# DiveComputer_STM32.net
KiCad netlist of a schematic drawn in EAGLE
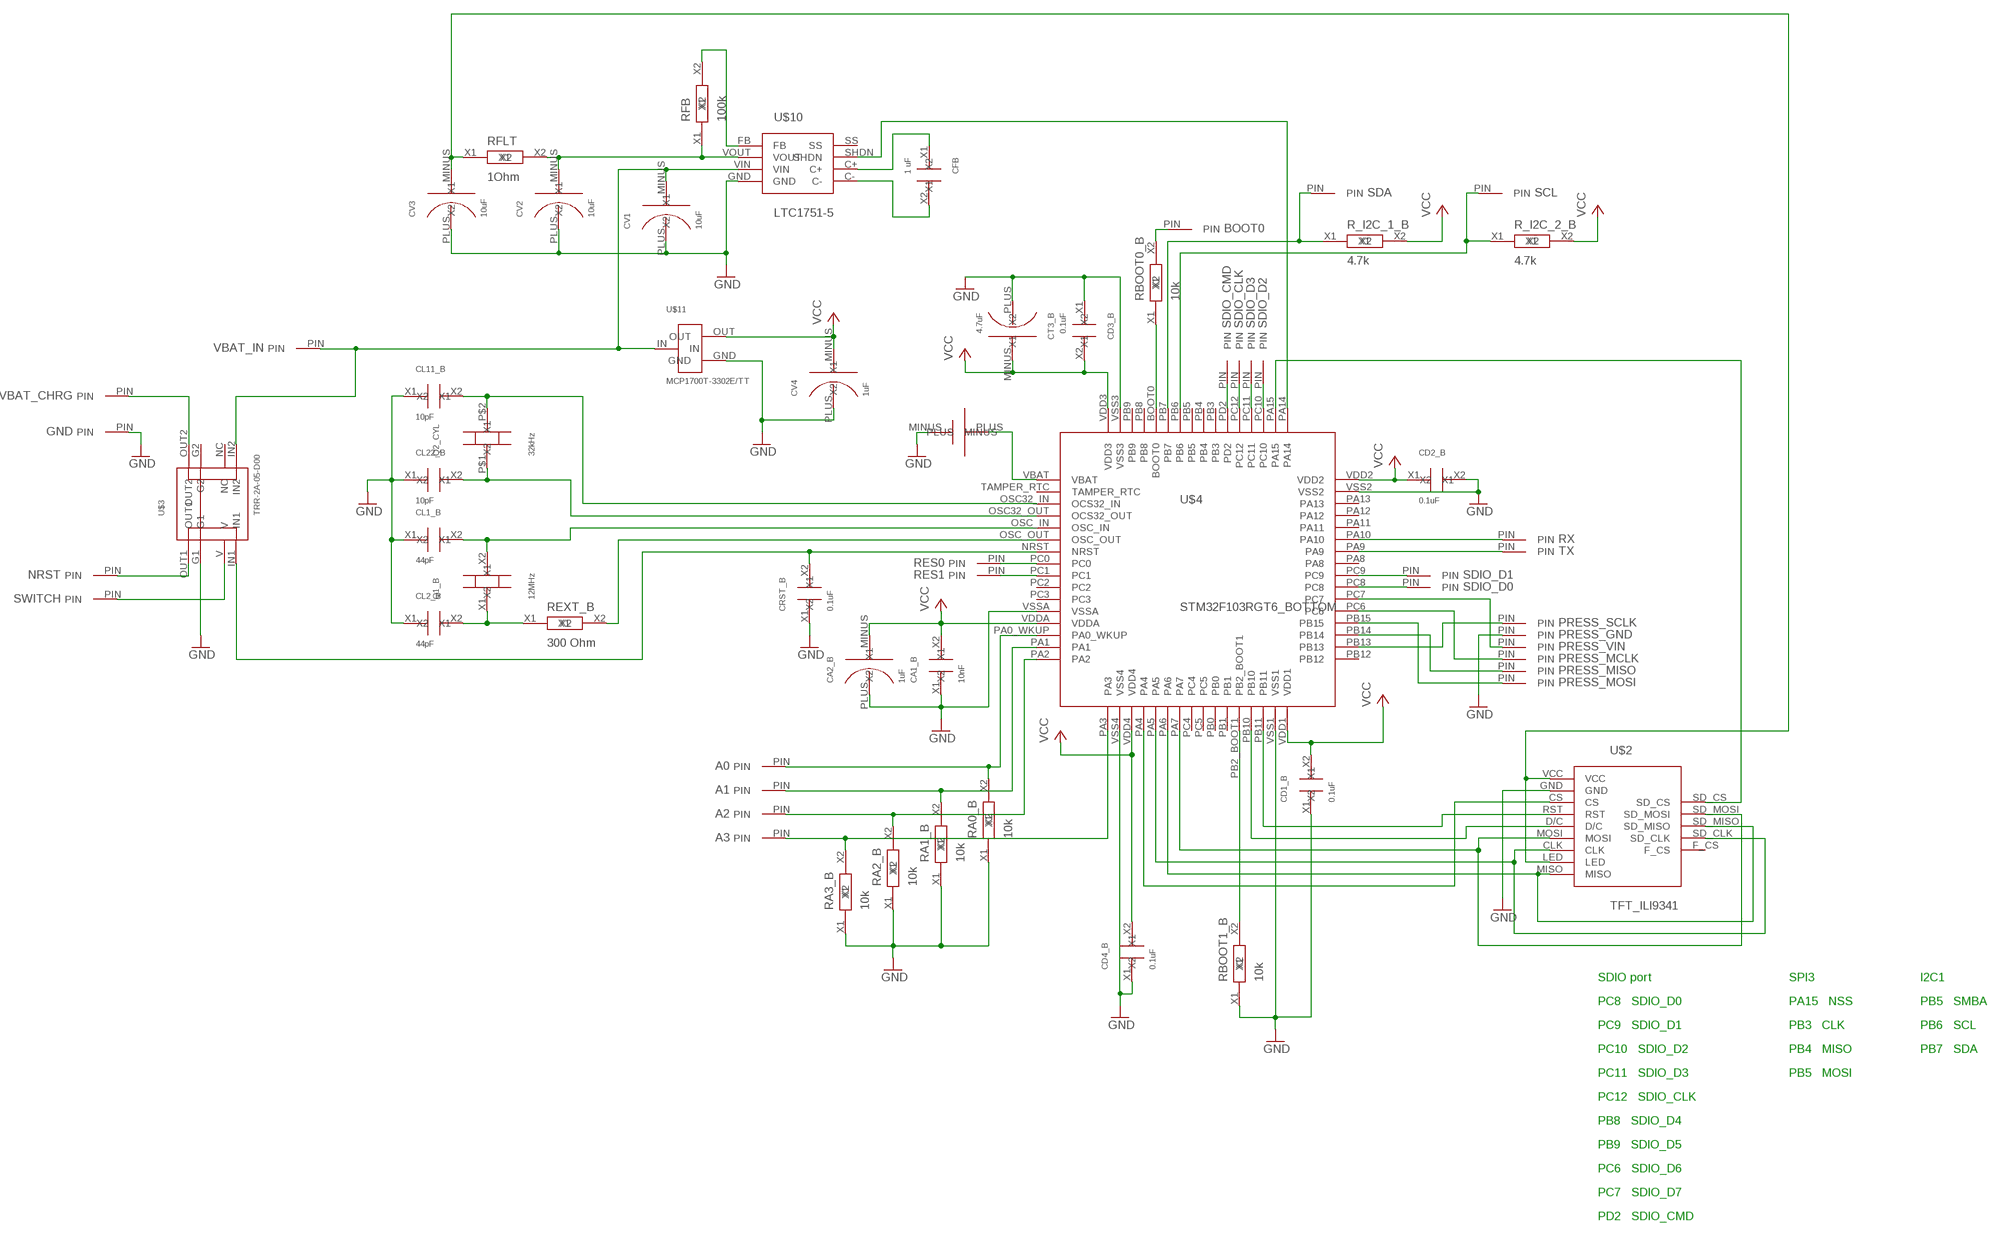
[diagram p0: schematic, sheet 1]

(export (version "E")
  (design (tool "Eeschema 10.0.6"))
  (components
    (comp (ref "A0")
      (value "PIN")
      (footprint "eagle-import:PIN")
      (libsource (lib "eagle-import") (part "PIN"))
    )
    (comp (ref "A1")
      (value "PIN")
      (footprint "eagle-import:PIN")
      (libsource (lib "eagle-import") (part "PIN"))
    )
    (comp (ref "A2")
      (value "PIN")
      (footprint "eagle-import:PIN")
      (libsource (lib "eagle-import") (part "PIN"))
    )
    (comp (ref "A3")
      (value "PIN")
      (footprint "eagle-import:PIN")
      (libsource (lib "eagle-import") (part "PIN"))
    )
    (comp (ref "BOOT0")
      (value "PIN")
      (footprint "eagle-import:PIN")
      (libsource (lib "eagle-import") (part "PIN"))
    )
    (comp (ref "CA1_B")
      (value "10nF")
      (footprint "eagle-import:SMD_2.1X1.25_BOTTOM")
      (libsource (lib "eagle-import") (part "C_SMD_2.1X1.25_BOTTOM"))
    )
    (comp (ref "CA2_B")
      (value "1uF")
      (footprint "eagle-import:C_SMD_TA_A_BOTTOM")
      (libsource (lib "eagle-import") (part "C_SMD_TA_A_BOTTOM"))
    )
    (comp (ref "CD1_B")
      (value "0.1uF")
      (footprint "eagle-import:SMD_2.1X1.25_BOTTOM")
      (libsource (lib "eagle-import") (part "C_SMD_2.1X1.25_BOTTOM"))
    )
    (comp (ref "CD2_B")
      (value "0.1uF")
      (footprint "eagle-import:SMD_2.1X1.25_BOTTOM")
      (libsource (lib "eagle-import") (part "C_SMD_2.1X1.25_BOTTOM"))
    )
    (comp (ref "CD3_B")
      (value "0.1uF")
      (footprint "eagle-import:SMD_2.1X1.25_BOTTOM")
      (libsource (lib "eagle-import") (part "C_SMD_2.1X1.25_BOTTOM"))
    )
    (comp (ref "CD4_B")
      (value "0.1uF")
      (footprint "eagle-import:SMD_2.1X1.25_BOTTOM")
      (libsource (lib "eagle-import") (part "C_SMD_2.1X1.25_BOTTOM"))
    )
    (comp (ref "CFB")
      (value "1 uF")
      (footprint "eagle-import:SMD_2.1X1.25")
      (libsource (lib "eagle-import") (part "C_SMD_2.1X1.25"))
    )
    (comp (ref "CL1_B")
      (value "44pF")
      (footprint "eagle-import:SMD_2.1X1.25_BOTTOM")
      (libsource (lib "eagle-import") (part "C_SMD_2.1X1.25_BOTTOM"))
    )
    (comp (ref "CL2_B")
      (value "44pF")
      (footprint "eagle-import:SMD_2.1X1.25_BOTTOM")
      (libsource (lib "eagle-import") (part "C_SMD_2.1X1.25_BOTTOM"))
    )
    (comp (ref "CL11_B")
      (value "10pF")
      (footprint "eagle-import:SMD_2.1X1.25_BOTTOM")
      (libsource (lib "eagle-import") (part "C_SMD_2.1X1.25_BOTTOM"))
    )
    (comp (ref "CL22_B")
      (value "10pF")
      (footprint "eagle-import:SMD_2.1X1.25_BOTTOM")
      (libsource (lib "eagle-import") (part "C_SMD_2.1X1.25_BOTTOM"))
    )
    (comp (ref "CRST_B")
      (value "0.1uF")
      (footprint "eagle-import:SMD_2.1X1.25_BOTTOM")
      (libsource (lib "eagle-import") (part "C_SMD_2.1X1.25_BOTTOM"))
    )
    (comp (ref "CT3_B")
      (value "4.7uF")
      (footprint "eagle-import:C_SMD_TA_A_BOTTOM")
      (libsource (lib "eagle-import") (part "C_SMD_TA_A_BOTTOM"))
    )
    (comp (ref "CV1")
      (value "10uF")
      (footprint "eagle-import:C_SMD_TA_A")
      (libsource (lib "eagle-import") (part "C_SMD_TA_A"))
    )
    (comp (ref "CV2")
      (value "10uF")
      (footprint "eagle-import:C_SMD_TA_A")
      (libsource (lib "eagle-import") (part "C_SMD_TA_A"))
    )
    (comp (ref "CV3")
      (value "10uF")
      (footprint "eagle-import:C_SMD_TA_A")
      (libsource (lib "eagle-import") (part "C_SMD_TA_A"))
    )
    (comp (ref "CV4")
      (value "1uF")
      (footprint "eagle-import:C_SMD_TA_A")
      (libsource (lib "eagle-import") (part "C_SMD_TA_A"))
    )
    (comp (ref "GND")
      (value "PIN")
      (footprint "eagle-import:PIN")
      (libsource (lib "eagle-import") (part "PIN"))
    )
    (comp (ref "NRST")
      (value "PIN")
      (footprint "eagle-import:PIN")
      (libsource (lib "eagle-import") (part "PIN"))
    )
    (comp (ref "PRESS_GND")
      (value "PIN")
      (footprint "eagle-import:PIN")
      (libsource (lib "eagle-import") (part "PIN"))
    )
    (comp (ref "PRESS_MCLK")
      (value "PIN")
      (footprint "eagle-import:PIN")
      (libsource (lib "eagle-import") (part "PIN"))
    )
    (comp (ref "PRESS_MISO")
      (value "PIN")
      (footprint "eagle-import:PIN")
      (libsource (lib "eagle-import") (part "PIN"))
    )
    (comp (ref "PRESS_MOSI")
      (value "PIN")
      (footprint "eagle-import:PIN")
      (libsource (lib "eagle-import") (part "PIN"))
    )
    (comp (ref "PRESS_SCLK")
      (value "PIN")
      (footprint "eagle-import:PIN")
      (libsource (lib "eagle-import") (part "PIN"))
    )
    (comp (ref "PRESS_VIN")
      (value "PIN")
      (footprint "eagle-import:PIN")
      (libsource (lib "eagle-import") (part "PIN"))
    )
    (comp (ref "Q1_B")
      (value "12MHz")
      (footprint "eagle-import:QUARTZ_SMD_BOTTOM")
      (libsource (lib "eagle-import") (part "QUARTZ_SMD_BOTTOM"))
    )
    (comp (ref "Q2_CYL")
      (value "32kHz")
      (footprint "eagle-import:QUARTZ_CYL")
      (libsource (lib "eagle-import") (part "QUARTZ_CYL"))
    )
    (comp (ref "RA0_B")
      (value "10k")
      (footprint "eagle-import:SMD_2.1X1.25_BOTTOM")
      (libsource (lib "eagle-import") (part "R_SMD_2.1X1.25_BOTTOM"))
    )
    (comp (ref "RA1_B")
      (value "10k")
      (footprint "eagle-import:SMD_2.1X1.25_BOTTOM")
      (libsource (lib "eagle-import") (part "R_SMD_2.1X1.25_BOTTOM"))
    )
    (comp (ref "RA2_B")
      (value "10k")
      (footprint "eagle-import:SMD_2.1X1.25_BOTTOM")
      (libsource (lib "eagle-import") (part "R_SMD_2.1X1.25_BOTTOM"))
    )
    (comp (ref "RA3_B")
      (value "10k")
      (footprint "eagle-import:SMD_2.1X1.25_BOTTOM")
      (libsource (lib "eagle-import") (part "R_SMD_2.1X1.25_BOTTOM"))
    )
    (comp (ref "RBOOT0_B")
      (value "10k")
      (footprint "eagle-import:SMD_2.1X1.25_BOTTOM")
      (libsource (lib "eagle-import") (part "R_SMD_2.1X1.25_BOTTOM"))
    )
    (comp (ref "RBOOT1_B")
      (value "10k")
      (footprint "eagle-import:SMD_2.1X1.25_BOTTOM")
      (libsource (lib "eagle-import") (part "R_SMD_2.1X1.25_BOTTOM"))
    )
    (comp (ref "RES0")
      (value "PIN")
      (footprint "eagle-import:PIN")
      (libsource (lib "eagle-import") (part "PIN"))
    )
    (comp (ref "RES1")
      (value "PIN")
      (footprint "eagle-import:PIN")
      (libsource (lib "eagle-import") (part "PIN"))
    )
    (comp (ref "REXT_B")
      (value "300 Ohm")
      (footprint "eagle-import:SMD_2.1X1.25_BOTTOM")
      (libsource (lib "eagle-import") (part "R_SMD_2.1X1.25_BOTTOM"))
    )
    (comp (ref "RFB")
      (value "100k")
      (footprint "eagle-import:SMD_2.1X1.25")
      (libsource (lib "eagle-import") (part "R_SMD_2.1X1.25"))
    )
    (comp (ref "RFLT")
      (value "1Ohm")
      (footprint "eagle-import:SMD_2.1X1.25")
      (libsource (lib "eagle-import") (part "R_SMD_2.1X1.25"))
    )
    (comp (ref "RX")
      (value "PIN")
      (footprint "eagle-import:PIN")
      (libsource (lib "eagle-import") (part "PIN"))
    )
    (comp (ref "R_I2C_1_B")
      (value "4.7k")
      (footprint "eagle-import:SMD_2.1X1.25_BOTTOM")
      (libsource (lib "eagle-import") (part "R_SMD_2.1X1.25_BOTTOM"))
    )
    (comp (ref "R_I2C_2_B")
      (value "4.7k")
      (footprint "eagle-import:SMD_2.1X1.25_BOTTOM")
      (libsource (lib "eagle-import") (part "R_SMD_2.1X1.25_BOTTOM"))
    )
    (comp (ref "SCL")
      (value "PIN")
      (footprint "eagle-import:PIN")
      (libsource (lib "eagle-import") (part "PIN"))
    )
    (comp (ref "SDA")
      (value "PIN")
      (footprint "eagle-import:PIN")
      (libsource (lib "eagle-import") (part "PIN"))
    )
    (comp (ref "SDIO_CLK")
      (value "PIN")
      (footprint "eagle-import:PIN")
      (libsource (lib "eagle-import") (part "PIN"))
    )
    (comp (ref "SDIO_CMD")
      (value "PIN")
      (footprint "eagle-import:PIN")
      (libsource (lib "eagle-import") (part "PIN"))
    )
    (comp (ref "SDIO_D0")
      (value "PIN")
      (footprint "eagle-import:PIN")
      (libsource (lib "eagle-import") (part "PIN"))
    )
    (comp (ref "SDIO_D1")
      (value "PIN")
      (footprint "eagle-import:PIN")
      (libsource (lib "eagle-import") (part "PIN"))
    )
    (comp (ref "SDIO_D2")
      (value "PIN")
      (footprint "eagle-import:PIN")
      (libsource (lib "eagle-import") (part "PIN"))
    )
    (comp (ref "SDIO_D3")
      (value "PIN")
      (footprint "eagle-import:PIN")
      (libsource (lib "eagle-import") (part "PIN"))
    )
    (comp (ref "SWITCH")
      (value "PIN")
      (footprint "eagle-import:PIN")
      (libsource (lib "eagle-import") (part "PIN"))
    )
    (comp (ref "TX")
      (value "PIN")
      (footprint "eagle-import:PIN")
      (libsource (lib "eagle-import") (part "PIN"))
    )
    (comp (ref "U$1")
      (value "VBAT")
      (footprint "eagle-import:VBAT")
      (libsource (lib "eagle-import") (part "VBAT"))
    )
    (comp (ref "U$2")
      (value "TFT_ILI9341")
      (footprint "eagle-import:TFT_ILI9341")
      (libsource (lib "eagle-import") (part "TFT_ILI9341"))
    )
    (comp (ref "U$3")
      (value "TRR-2A-05-D00")
      (footprint "eagle-import:TRR-2A-05-D00")
      (libsource (lib "eagle-import") (part "TRR-2A-05-D00"))
    )
    (comp (ref "U$4")
      (value "STM32F103RGT6_BOTTOM")
      (footprint "eagle-import:STM32F103RGT6_BOTTOM")
      (libsource (lib "eagle-import") (part "STM32F103RGT6_BOTTOM"))
    )
    (comp (ref "U$10")
      (value "LTC1751-5")
      (footprint "eagle-import:LTC1751-5")
      (libsource (lib "eagle-import") (part "LTC1751-5"))
    )
    (comp (ref "U$11")
      (value "MCP1700T-3302E/TT")
      (footprint "eagle-import:MCP1700T-3302E_TT")
      (libsource (lib "eagle-import") (part "MCP1700T-3302E/TT"))
    )
    (comp (ref "VBAT_CHRG")
      (value "PIN")
      (footprint "eagle-import:PIN")
      (libsource (lib "eagle-import") (part "PIN"))
    )
    (comp (ref "VBAT_IN")
      (value "PIN")
      (footprint "eagle-import:PIN")
      (libsource (lib "eagle-import") (part "PIN"))
    )
  )
  (nets
    (net (code "1") (name "GND") (class "Default")
      (node (ref "CA1_B") (pin "X1") (pinfunction "X1_X1") (pintype "bidirectional"))
      (node (ref "CA2_B") (pin "PLUS") (pinfunction "X1_PLUS") (pintype "bidirectional"))
      (node (ref "CD1_B") (pin "X1") (pinfunction "X1_X1") (pintype "bidirectional"))
      (node (ref "CD2_B") (pin "X2") (pinfunction "X2_X2") (pintype "bidirectional"))
      (node (ref "CD3_B") (pin "X1") (pinfunction "X1_X1") (pintype "bidirectional"))
      (node (ref "CD4_B") (pin "X1") (pinfunction "X1_X1") (pintype "bidirectional"))
      (node (ref "CL11_B") (pin "X1") (pinfunction "X1_X1") (pintype "bidirectional"))
      (node (ref "CL1_B") (pin "X1") (pinfunction "X1_X1") (pintype "bidirectional"))
      (node (ref "CL22_B") (pin "X1") (pinfunction "X1_X1") (pintype "bidirectional"))
      (node (ref "CL2_B") (pin "X1") (pinfunction "X1_X1") (pintype "bidirectional"))
      (node (ref "CRST_B") (pin "X1") (pinfunction "X1_X1") (pintype "bidirectional"))
      (node (ref "CT3_B") (pin "PLUS") (pinfunction "X1_PLUS") (pintype "bidirectional"))
      (node (ref "CV1") (pin "PLUS") (pinfunction "X1_PLUS") (pintype "bidirectional"))
      (node (ref "CV2") (pin "PLUS") (pinfunction "X1_PLUS") (pintype "bidirectional"))
      (node (ref "CV3") (pin "PLUS") (pinfunction "X1_PLUS") (pintype "bidirectional"))
      (node (ref "CV4") (pin "PLUS") (pinfunction "X1_PLUS") (pintype "bidirectional"))
      (node (ref "GND") (pin "PIN") (pinfunction "PIN_PIN") (pintype "bidirectional"))
      (node (ref "PRESS_GND") (pin "PIN") (pinfunction "PIN_PIN") (pintype "bidirectional"))
      (node (ref "RA0_B") (pin "X1") (pinfunction "X1_X1") (pintype "bidirectional"))
      (node (ref "RA1_B") (pin "X1") (pinfunction "X1_X1") (pintype "bidirectional"))
      (node (ref "RA2_B") (pin "X1") (pinfunction "X1_X1") (pintype "bidirectional"))
      (node (ref "RA3_B") (pin "X1") (pinfunction "X1_X1") (pintype "bidirectional"))
      (node (ref "RBOOT1_B") (pin "X1") (pinfunction "X1_X1") (pintype "bidirectional"))
      (node (ref "U$1") (pin "MINUS") (pinfunction "MINUS_MINUS") (pintype "bidirectional"))
      (node (ref "U$10") (pin "GND") (pinfunction "GND_GND") (pintype "bidirectional"))
      (node (ref "U$11") (pin "GND") (pinfunction "GND_GND") (pintype "bidirectional"))
      (node (ref "U$2") (pin "GND") (pinfunction "GND_GND") (pintype "bidirectional"))
      (node (ref "U$3") (pin "G1") (pinfunction "G1_G1") (pintype "bidirectional"))
      (node (ref "U$4") (pin "VSS1") (pinfunction "VSS1_VSS1") (pintype "bidirectional"))
      (node (ref "U$4") (pin "VSS2") (pinfunction "VSS2_VSS2") (pintype "bidirectional"))
      (node (ref "U$4") (pin "VSS3") (pinfunction "VSS3_VSS3") (pintype "bidirectional"))
      (node (ref "U$4") (pin "VSS4") (pinfunction "VSS4_VSS4") (pintype "bidirectional"))
      (node (ref "U$4") (pin "VSSA") (pinfunction "VSSA_VSSA") (pintype "bidirectional"))
    )
    (net (code "2") (name "Net-(A0-PadPIN)") (class "Default")
      (node (ref "A0") (pin "PIN") (pinfunction "PIN_PIN") (pintype "bidirectional"))
      (node (ref "RA0_B") (pin "X2") (pinfunction "X2_X2") (pintype "bidirectional"))
      (node (ref "U$4") (pin "PA0_WKUP") (pinfunction "PA0_WKUP_PA0_WKUP") (pintype "bidirectional"))
    )
    (net (code "3") (name "Net-(A1-PadPIN)") (class "Default")
      (node (ref "A1") (pin "PIN") (pinfunction "PIN_PIN") (pintype "bidirectional"))
      (node (ref "RA1_B") (pin "X2") (pinfunction "X2_X2") (pintype "bidirectional"))
      (node (ref "U$4") (pin "PA1") (pinfunction "PA1_PA1") (pintype "bidirectional"))
    )
    (net (code "4") (name "Net-(A2-PadPIN)") (class "Default")
      (node (ref "A2") (pin "PIN") (pinfunction "PIN_PIN") (pintype "bidirectional"))
      (node (ref "RA2_B") (pin "X2") (pinfunction "X2_X2") (pintype "bidirectional"))
      (node (ref "U$4") (pin "PA2") (pinfunction "PA2_PA2") (pintype "bidirectional"))
    )
    (net (code "5") (name "Net-(A3-PadPIN)") (class "Default")
      (node (ref "A3") (pin "PIN") (pinfunction "PIN_PIN") (pintype "bidirectional"))
      (node (ref "RA3_B") (pin "X2") (pinfunction "X2_X2") (pintype "bidirectional"))
      (node (ref "U$4") (pin "PA3") (pinfunction "PA3_PA3") (pintype "bidirectional"))
    )
    (net (code "6") (name "Net-(BOOT0-PadPIN)") (class "Default")
      (node (ref "BOOT0") (pin "PIN") (pinfunction "PIN_PIN") (pintype "bidirectional"))
      (node (ref "RBOOT0_B") (pin "X2") (pinfunction "X2_X2") (pintype "bidirectional"))
    )
    (net (code "7") (name "Net-(CFB-PadX1)") (class "Default")
      (node (ref "CFB") (pin "X1") (pinfunction "X1_X1") (pintype "bidirectional"))
      (node (ref "U$10") (pin "C+") (pinfunction "C+_C+") (pintype "bidirectional"))
    )
    (net (code "8") (name "Net-(CFB-PadX2)") (class "Default")
      (node (ref "CFB") (pin "X2") (pinfunction "X2_X2") (pintype "bidirectional"))
      (node (ref "U$10") (pin "C-") (pinfunction "C-_C-") (pintype "bidirectional"))
    )
    (net (code "9") (name "Net-(CL1_B-PadX2)") (class "Default")
      (node (ref "CL1_B") (pin "X2") (pinfunction "X2_X2") (pintype "bidirectional"))
      (node (ref "Q1_B") (pin "X2") (pinfunction "X2_X2") (pintype "bidirectional"))
      (node (ref "U$4") (pin "OSC_IN") (pinfunction "OSC_IN_OSC_IN") (pintype "bidirectional"))
    )
    (net (code "10") (name "Net-(CL2_B-PadX2)") (class "Default")
      (node (ref "CL2_B") (pin "X2") (pinfunction "X2_X2") (pintype "bidirectional"))
      (node (ref "Q1_B") (pin "X1") (pinfunction "X1_X1") (pintype "bidirectional"))
      (node (ref "REXT_B") (pin "X1") (pinfunction "X1_X1") (pintype "bidirectional"))
    )
    (net (code "11") (name "Net-(CRST_B-PadX2)") (class "Default")
      (node (ref "CRST_B") (pin "X2") (pinfunction "X2_X2") (pintype "bidirectional"))
      (node (ref "U$3") (pin "IN1") (pinfunction "IN1_IN1") (pintype "bidirectional"))
      (node (ref "U$4") (pin "NRST") (pinfunction "NRST_NRST") (pintype "bidirectional"))
    )
    (net (code "12") (name "Net-(CV1-X2)") (class "Default")
      (node (ref "CV1") (pin "MINUS") (pinfunction "X2_MINUS") (pintype "bidirectional"))
      (node (ref "U$10") (pin "VIN") (pinfunction "VIN_VIN") (pintype "bidirectional"))
      (node (ref "U$11") (pin "IN") (pinfunction "IN_IN") (pintype "bidirectional"))
      (node (ref "U$3") (pin "IN2") (pinfunction "IN2_IN2") (pintype "bidirectional"))
      (node (ref "VBAT_IN") (pin "PIN") (pinfunction "PIN_PIN") (pintype "bidirectional"))
    )
    (net (code "13") (name "Net-(CV2-X2)") (class "Default")
      (node (ref "CV2") (pin "MINUS") (pinfunction "X2_MINUS") (pintype "bidirectional"))
      (node (ref "RFB") (pin "X1") (pinfunction "X1_X1") (pintype "bidirectional"))
      (node (ref "RFLT") (pin "X2") (pinfunction "X2_X2") (pintype "bidirectional"))
      (node (ref "U$10") (pin "VOUT") (pinfunction "VOUT_VOUT") (pintype "bidirectional"))
    )
    (net (code "14") (name "Net-(CV3-X2)") (class "Default")
      (node (ref "CV3") (pin "MINUS") (pinfunction "X2_MINUS") (pintype "bidirectional"))
      (node (ref "RFLT") (pin "X1") (pinfunction "X1_X1") (pintype "bidirectional"))
      (node (ref "U$2") (pin "LED") (pinfunction "LED_LED") (pintype "bidirectional"))
      (node (ref "U$2") (pin "VCC") (pinfunction "VCC_VCC") (pintype "bidirectional"))
    )
    (net (code "15") (name "Net-(NRST-PadPIN)") (class "Default")
      (node (ref "NRST") (pin "PIN") (pinfunction "PIN_PIN") (pintype "bidirectional"))
      (node (ref "U$3") (pin "OUT1") (pinfunction "OUT1_OUT1") (pintype "bidirectional"))
    )
    (net (code "16") (name "Net-(PRESS_MCLK-PadPIN)") (class "Default")
      (node (ref "PRESS_MCLK") (pin "PIN") (pinfunction "PIN_PIN") (pintype "bidirectional"))
      (node (ref "U$4") (pin "PC6") (pinfunction "PC6_PC6") (pintype "bidirectional"))
    )
    (net (code "17") (name "Net-(PRESS_MISO-PadPIN)") (class "Default")
      (node (ref "PRESS_MISO") (pin "PIN") (pinfunction "PIN_PIN") (pintype "bidirectional"))
      (node (ref "U$4") (pin "PB14") (pinfunction "PB14_PB14") (pintype "bidirectional"))
    )
    (net (code "18") (name "Net-(PRESS_MOSI-PadPIN)") (class "Default")
      (node (ref "PRESS_MOSI") (pin "PIN") (pinfunction "PIN_PIN") (pintype "bidirectional"))
      (node (ref "U$4") (pin "PB15") (pinfunction "PB15_PB15") (pintype "bidirectional"))
    )
    (net (code "19") (name "Net-(PRESS_SCLK-PadPIN)") (class "Default")
      (node (ref "PRESS_SCLK") (pin "PIN") (pinfunction "PIN_PIN") (pintype "bidirectional"))
      (node (ref "U$4") (pin "PB13") (pinfunction "PB13_PB13") (pintype "bidirectional"))
    )
    (net (code "20") (name "Net-(PRESS_VIN-PadPIN)") (class "Default")
      (node (ref "PRESS_VIN") (pin "PIN") (pinfunction "PIN_PIN") (pintype "bidirectional"))
      (node (ref "U$4") (pin "PC7") (pinfunction "PC7_PC7") (pintype "bidirectional"))
    )
    (net (code "21") (name "Net-(Q2_CYL-X1)") (class "Default")
      (node (ref "CL22_B") (pin "X2") (pinfunction "X2_X2") (pintype "bidirectional"))
      (node (ref "Q2_CYL") (pin "P$1") (pinfunction "X1_P$1") (pintype "bidirectional"))
      (node (ref "U$4") (pin "OSC32_OUT") (pinfunction "OCS32_OUT_OSC32_OUT") (pintype "bidirectional"))
    )
    (net (code "22") (name "Net-(Q2_CYL-X2)") (class "Default")
      (node (ref "CL11_B") (pin "X2") (pinfunction "X2_X2") (pintype "bidirectional"))
      (node (ref "Q2_CYL") (pin "P$2") (pinfunction "X2_P$2") (pintype "bidirectional"))
      (node (ref "U$4") (pin "OSC32_IN") (pinfunction "OCS32_IN_OSC32_IN") (pintype "bidirectional"))
    )
    (net (code "23") (name "Net-(RBOOT0_B-PadX1)") (class "Default")
      (node (ref "RBOOT0_B") (pin "X1") (pinfunction "X1_X1") (pintype "bidirectional"))
      (node (ref "U$4") (pin "BOOT0") (pinfunction "BOOT0_BOOT0") (pintype "bidirectional"))
    )
    (net (code "24") (name "Net-(RBOOT1_B-PadX2)") (class "Default")
      (node (ref "RBOOT1_B") (pin "X2") (pinfunction "X2_X2") (pintype "bidirectional"))
      (node (ref "U$4") (pin "PB2_BOOT1") (pinfunction "PB2_BOOT1_PB2_BOOT1") (pintype "bidirectional"))
    )
    (net (code "25") (name "Net-(RES0-PadPIN)") (class "Default")
      (node (ref "RES0") (pin "PIN") (pinfunction "PIN_PIN") (pintype "bidirectional"))
      (node (ref "U$4") (pin "PC0") (pinfunction "PC0_PC0") (pintype "bidirectional"))
    )
    (net (code "26") (name "Net-(RES1-PadPIN)") (class "Default")
      (node (ref "RES1") (pin "PIN") (pinfunction "PIN_PIN") (pintype "bidirectional"))
      (node (ref "U$4") (pin "PC1") (pinfunction "PC1_PC1") (pintype "bidirectional"))
    )
    (net (code "27") (name "Net-(REXT_B-PadX2)") (class "Default")
      (node (ref "REXT_B") (pin "X2") (pinfunction "X2_X2") (pintype "bidirectional"))
      (node (ref "U$4") (pin "OSC_OUT") (pinfunction "OSC_OUT_OSC_OUT") (pintype "bidirectional"))
    )
    (net (code "28") (name "Net-(RFB-PadX2)") (class "Default")
      (node (ref "RFB") (pin "X2") (pinfunction "X2_X2") (pintype "bidirectional"))
      (node (ref "U$10") (pin "FB") (pinfunction "FB_FB") (pintype "bidirectional"))
    )
    (net (code "29") (name "Net-(RX-PadPIN)") (class "Default")
      (node (ref "RX") (pin "PIN") (pinfunction "PIN_PIN") (pintype "bidirectional"))
      (node (ref "U$4") (pin "PA10") (pinfunction "PA10_PA10") (pintype "bidirectional"))
    )
    (net (code "30") (name "Net-(R_I2C_1_B-PadX1)") (class "Default")
      (node (ref "R_I2C_1_B") (pin "X1") (pinfunction "X1_X1") (pintype "bidirectional"))
      (node (ref "SDA") (pin "PIN") (pinfunction "PIN_PIN") (pintype "bidirectional"))
      (node (ref "U$4") (pin "PB7") (pinfunction "PB7_PB7") (pintype "bidirectional"))
    )
    (net (code "31") (name "Net-(R_I2C_2_B-PadX1)") (class "Default")
      (node (ref "R_I2C_2_B") (pin "X1") (pinfunction "X1_X1") (pintype "bidirectional"))
      (node (ref "SCL") (pin "PIN") (pinfunction "PIN_PIN") (pintype "bidirectional"))
      (node (ref "U$4") (pin "PB6") (pinfunction "PB6_PB6") (pintype "bidirectional"))
    )
    (net (code "32") (name "Net-(SDIO_CLK-PadPIN)") (class "Default")
      (node (ref "SDIO_CLK") (pin "PIN") (pinfunction "PIN_PIN") (pintype "bidirectional"))
      (node (ref "U$4") (pin "PC12") (pinfunction "PC12_PC12") (pintype "bidirectional"))
    )
    (net (code "33") (name "Net-(SDIO_CMD-PadPIN)") (class "Default")
      (node (ref "SDIO_CMD") (pin "PIN") (pinfunction "PIN_PIN") (pintype "bidirectional"))
      (node (ref "U$4") (pin "PD2") (pinfunction "PD2_PD2") (pintype "bidirectional"))
    )
    (net (code "34") (name "Net-(SDIO_D0-PadPIN)") (class "Default")
      (node (ref "SDIO_D0") (pin "PIN") (pinfunction "PIN_PIN") (pintype "bidirectional"))
      (node (ref "U$4") (pin "PC8") (pinfunction "PC8_PC8") (pintype "bidirectional"))
    )
    (net (code "35") (name "Net-(SDIO_D1-PadPIN)") (class "Default")
      (node (ref "SDIO_D1") (pin "PIN") (pinfunction "PIN_PIN") (pintype "bidirectional"))
      (node (ref "U$4") (pin "PC9") (pinfunction "PC9_PC9") (pintype "bidirectional"))
    )
    (net (code "36") (name "Net-(SDIO_D2-PadPIN)") (class "Default")
      (node (ref "SDIO_D2") (pin "PIN") (pinfunction "PIN_PIN") (pintype "bidirectional"))
      (node (ref "U$4") (pin "PC10") (pinfunction "PC10_PC10") (pintype "bidirectional"))
    )
    (net (code "37") (name "Net-(SDIO_D3-PadPIN)") (class "Default")
      (node (ref "SDIO_D3") (pin "PIN") (pinfunction "PIN_PIN") (pintype "bidirectional"))
      (node (ref "U$4") (pin "PC11") (pinfunction "PC11_PC11") (pintype "bidirectional"))
    )
    (net (code "38") (name "Net-(SWITCH-PadPIN)") (class "Default")
      (node (ref "SWITCH") (pin "PIN") (pinfunction "PIN_PIN") (pintype "bidirectional"))
      (node (ref "U$3") (pin "V") (pinfunction "V_V") (pintype "bidirectional"))
    )
    (net (code "39") (name "Net-(TX-PadPIN)") (class "Default")
      (node (ref "TX") (pin "PIN") (pinfunction "PIN_PIN") (pintype "bidirectional"))
      (node (ref "U$4") (pin "PA9") (pinfunction "PA9_PA9") (pintype "bidirectional"))
    )
    (net (code "40") (name "Net-(U$1-PadPLUS)") (class "Default")
      (node (ref "U$1") (pin "PLUS") (pinfunction "PLUS_PLUS") (pintype "bidirectional"))
      (node (ref "U$4") (pin "VBAT") (pinfunction "VBAT_VBAT") (pintype "bidirectional"))
    )
    (net (code "41") (name "Net-(U$2-PadCLK)") (class "Default")
      (node (ref "U$2") (pin "CLK") (pinfunction "CLK_CLK") (pintype "bidirectional"))
      (node (ref "U$2") (pin "SD_CLK") (pinfunction "SD_CLK_SD_CLK") (pintype "bidirectional"))
      (node (ref "U$4") (pin "PA5") (pinfunction "PA5_PA5") (pintype "bidirectional"))
    )
    (net (code "42") (name "Net-(U$2-PadCS)") (class "Default")
      (node (ref "U$2") (pin "CS") (pinfunction "CS_CS") (pintype "bidirectional"))
      (node (ref "U$4") (pin "PA4") (pinfunction "PA4_PA4") (pintype "bidirectional"))
    )
    (net (code "43") (name "Net-(U$2-PadD{slash}C)") (class "Default")
      (node (ref "U$2") (pin "D/C") (pinfunction "D/C_D/C") (pintype "bidirectional"))
      (node (ref "U$4") (pin "PB10") (pinfunction "PB10_PB10") (pintype "bidirectional"))
    )
    (net (code "44") (name "Net-(U$2-PadMISO)") (class "Default")
      (node (ref "U$2") (pin "MISO") (pinfunction "MISO_MISO") (pintype "bidirectional"))
      (node (ref "U$2") (pin "SD_MISO") (pinfunction "SD_MISO_SD_MISO") (pintype "bidirectional"))
      (node (ref "U$4") (pin "PA6") (pinfunction "PA6_PA6") (pintype "bidirectional"))
    )
    (net (code "45") (name "Net-(U$2-PadMOSI)") (class "Default")
      (node (ref "U$2") (pin "MOSI") (pinfunction "MOSI_MOSI") (pintype "bidirectional"))
      (node (ref "U$2") (pin "SD_MOSI") (pinfunction "SD_MOSI_SD_MOSI") (pintype "bidirectional"))
      (node (ref "U$4") (pin "PA7") (pinfunction "PA7_PA7") (pintype "bidirectional"))
    )
    (net (code "46") (name "Net-(U$2-PadRST)") (class "Default")
      (node (ref "U$2") (pin "RST") (pinfunction "RST_RST") (pintype "bidirectional"))
      (node (ref "U$4") (pin "PB11") (pinfunction "PB11_PB11") (pintype "bidirectional"))
    )
    (net (code "47") (name "Net-(U$2-PadSD_CS)") (class "Default")
      (node (ref "U$2") (pin "SD_CS") (pinfunction "SD_CS_SD_CS") (pintype "bidirectional"))
      (node (ref "U$4") (pin "PA15") (pinfunction "PA15_PA15") (pintype "bidirectional"))
    )
    (net (code "48") (name "Net-(U$3-PadOUT2)") (class "Default")
      (node (ref "U$3") (pin "OUT2") (pinfunction "OUT2_OUT2") (pintype "bidirectional"))
      (node (ref "VBAT_CHRG") (pin "PIN") (pinfunction "PIN_PIN") (pintype "bidirectional"))
    )
    (net (code "49") (name "Net-(U$10-PadSHDN)") (class "Default")
      (node (ref "U$10") (pin "SHDN") (pinfunction "SHDN_SHDN") (pintype "bidirectional"))
      (node (ref "U$4") (pin "PA14") (pinfunction "PA14_PA14") (pintype "bidirectional"))
    )
    (net (code "50") (name "VCC") (class "Default")
      (node (ref "CA1_B") (pin "X2") (pinfunction "X2_X2") (pintype "bidirectional"))
      (node (ref "CA2_B") (pin "MINUS") (pinfunction "X2_MINUS") (pintype "bidirectional"))
      (node (ref "CD1_B") (pin "X2") (pinfunction "X2_X2") (pintype "bidirectional"))
      (node (ref "CD2_B") (pin "X1") (pinfunction "X1_X1") (pintype "bidirectional"))
      (node (ref "CD3_B") (pin "X2") (pinfunction "X2_X2") (pintype "bidirectional"))
      (node (ref "CD4_B") (pin "X2") (pinfunction "X2_X2") (pintype "bidirectional"))
      (node (ref "CT3_B") (pin "MINUS") (pinfunction "X2_MINUS") (pintype "bidirectional"))
      (node (ref "CV4") (pin "MINUS") (pinfunction "X2_MINUS") (pintype "bidirectional"))
      (node (ref "R_I2C_1_B") (pin "X2") (pinfunction "X2_X2") (pintype "bidirectional"))
      (node (ref "R_I2C_2_B") (pin "X2") (pinfunction "X2_X2") (pintype "bidirectional"))
      (node (ref "U$11") (pin "OUT") (pinfunction "OUT_OUT") (pintype "bidirectional"))
      (node (ref "U$4") (pin "VDD1") (pinfunction "VDD1_VDD1") (pintype "bidirectional"))
      (node (ref "U$4") (pin "VDD2") (pinfunction "VDD2_VDD2") (pintype "bidirectional"))
      (node (ref "U$4") (pin "VDD3") (pinfunction "VDD3_VDD3") (pintype "bidirectional"))
      (node (ref "U$4") (pin "VDD4") (pinfunction "VDD4_VDD4") (pintype "bidirectional"))
      (node (ref "U$4") (pin "VDDA") (pinfunction "VDDA_VDDA") (pintype "bidirectional"))
    )
    (net (code "51") (name "unconnected-(U$2-PadF_CS)") (class "Default")
      (node (ref "U$2") (pin "F_CS") (pinfunction "F_CS_F_CS") (pintype "bidirectional"))
    )
    (net (code "52") (name "unconnected-(U$3-PadG2)") (class "Default")
      (node (ref "U$3") (pin "G2") (pinfunction "G2_G2") (pintype "bidirectional"))
    )
    (net (code "53") (name "unconnected-(U$3-PadNC)") (class "Default")
      (node (ref "U$3") (pin "NC") (pinfunction "NC_NC") (pintype "bidirectional"))
    )
    (net (code "54") (name "unconnected-(U$4-PadPA8)") (class "Default")
      (node (ref "U$4") (pin "PA8") (pinfunction "PA8_PA8") (pintype "bidirectional"))
    )
    (net (code "55") (name "unconnected-(U$4-PadPA11)") (class "Default")
      (node (ref "U$4") (pin "PA11") (pinfunction "PA11_PA11") (pintype "bidirectional"))
    )
    (net (code "56") (name "unconnected-(U$4-PadPA12)") (class "Default")
      (node (ref "U$4") (pin "PA12") (pinfunction "PA12_PA12") (pintype "bidirectional"))
    )
    (net (code "57") (name "unconnected-(U$4-PadPA13)") (class "Default")
      (node (ref "U$4") (pin "PA13") (pinfunction "PA13_PA13") (pintype "bidirectional"))
    )
    (net (code "58") (name "unconnected-(U$4-PadPB0)") (class "Default")
      (node (ref "U$4") (pin "PB0") (pinfunction "PB0_PB0") (pintype "bidirectional"))
    )
    (net (code "59") (name "unconnected-(U$4-PadPB1)") (class "Default")
      (node (ref "U$4") (pin "PB1") (pinfunction "PB1_PB1") (pintype "bidirectional"))
    )
    (net (code "60") (name "unconnected-(U$4-PadPB3)") (class "Default")
      (node (ref "U$4") (pin "PB3") (pinfunction "PB3_PB3") (pintype "bidirectional"))
    )
    (net (code "61") (name "unconnected-(U$4-PadPB4)") (class "Default")
      (node (ref "U$4") (pin "PB4") (pinfunction "PB4_PB4") (pintype "bidirectional"))
    )
    (net (code "62") (name "unconnected-(U$4-PadPB5)") (class "Default")
      (node (ref "U$4") (pin "PB5") (pinfunction "PB5_PB5") (pintype "bidirectional"))
    )
    (net (code "63") (name "unconnected-(U$4-PadPB8)") (class "Default")
      (node (ref "U$4") (pin "PB8") (pinfunction "PB8_PB8") (pintype "bidirectional"))
    )
    (net (code "64") (name "unconnected-(U$4-PadPB9)") (class "Default")
      (node (ref "U$4") (pin "PB9") (pinfunction "PB9_PB9") (pintype "bidirectional"))
    )
    (net (code "65") (name "unconnected-(U$4-PadPB12)") (class "Default")
      (node (ref "U$4") (pin "PB12") (pinfunction "PB12_PB12") (pintype "bidirectional"))
    )
    (net (code "66") (name "unconnected-(U$4-PadPC2)") (class "Default")
      (node (ref "U$4") (pin "PC2") (pinfunction "PC2_PC2") (pintype "bidirectional"))
    )
    (net (code "67") (name "unconnected-(U$4-PadPC3)") (class "Default")
      (node (ref "U$4") (pin "PC3") (pinfunction "PC3_PC3") (pintype "bidirectional"))
    )
    (net (code "68") (name "unconnected-(U$4-PadPC4)") (class "Default")
      (node (ref "U$4") (pin "PC4") (pinfunction "PC4_PC4") (pintype "bidirectional"))
    )
    (net (code "69") (name "unconnected-(U$4-PadPC5)") (class "Default")
      (node (ref "U$4") (pin "PC5") (pinfunction "PC5_PC5") (pintype "bidirectional"))
    )
    (net (code "70") (name "unconnected-(U$4-PadTAMPER_RTC)") (class "Default")
      (node (ref "U$4") (pin "TAMPER_RTC") (pinfunction "TAMPER_RTC_TAMPER_RTC") (pintype "bidirectional"))
    )
    (net (code "71") (name "unconnected-(U$10-PadSS)") (class "Default")
      (node (ref "U$10") (pin "SS") (pinfunction "SS_SS") (pintype "bidirectional"))
    )
  )
)
